# ESP8266_firstBringup.net
KiCad netlist of a schematic drawn in EAGLE
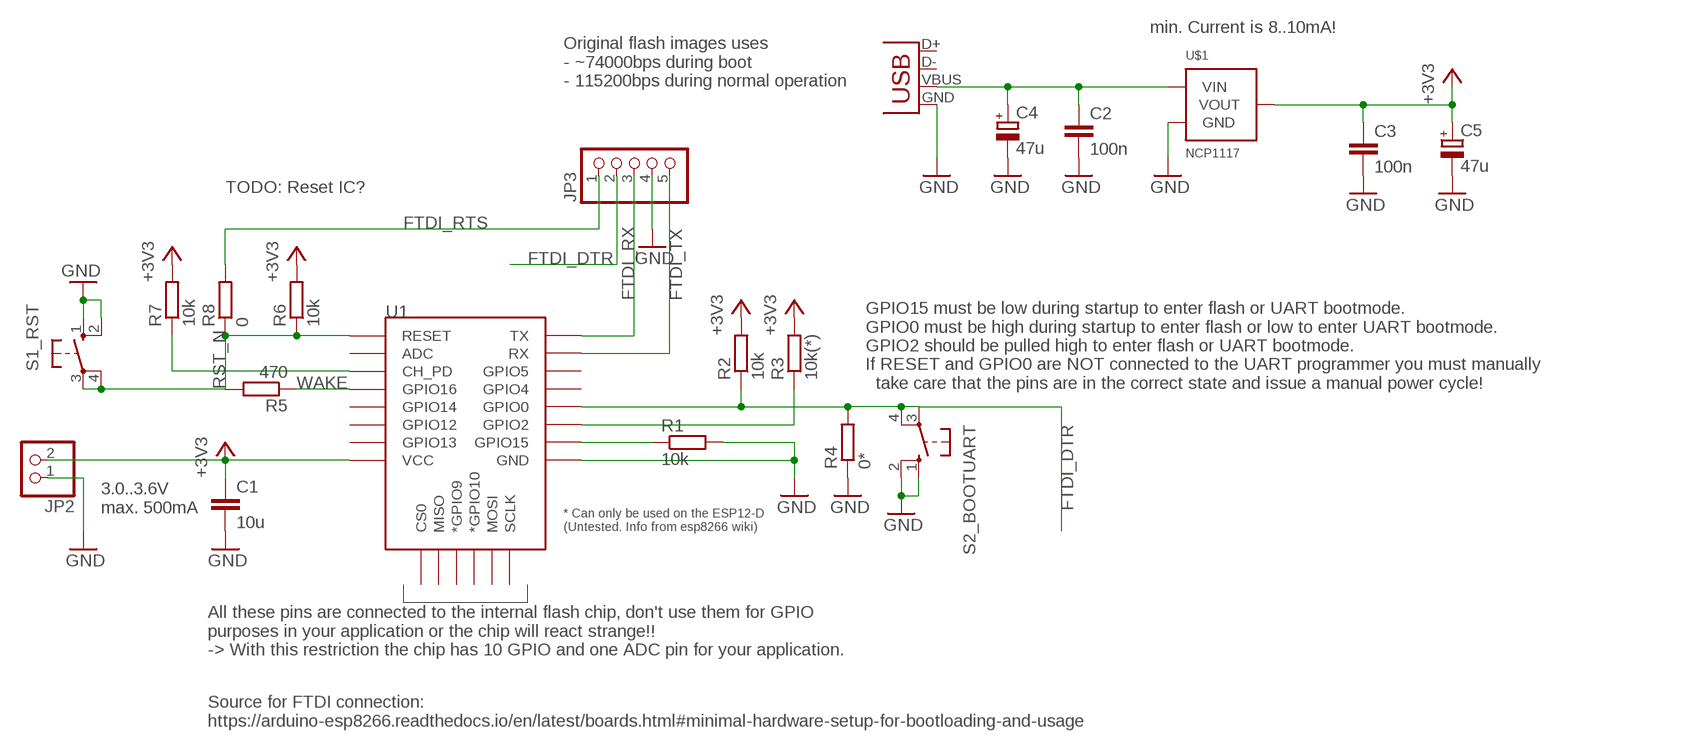
[diagram p0: schematic, sheet 1]

(export (version "E")
  (design (tool "Eeschema 10.0.6"))
  (components
    (comp (ref "C1")
      (value "10u")
      (footprint "eagle-import:C0805")
      (libsource (lib "eagle-import") (part "C-EUC0805"))
    )
    (comp (ref "C2")
      (value "100n")
      (footprint "eagle-import:C0603")
      (libsource (lib "eagle-import") (part "C-EUC0603"))
    )
    (comp (ref "C3")
      (value "100n")
      (footprint "eagle-import:C0603")
      (libsource (lib "eagle-import") (part "C-EUC0603"))
    )
    (comp (ref "C4")
      (value "47u")
      (footprint "eagle-import:E2,5-6")
      (libsource (lib "eagle-import") (part "CPOL-EUE2.5-6"))
    )
    (comp (ref "C5")
      (value "47u")
      (footprint "eagle-import:E2,5-6")
      (libsource (lib "eagle-import") (part "CPOL-EUE2.5-6"))
    )
    (comp (ref "JP2")
      (value "PINHD-1X2")
      (footprint "eagle-import:1X02")
      (libsource (lib "eagle-import") (part "PINHD-1X2"))
    )
    (comp (ref "JP3")
      (value "PINHD-1X5")
      (footprint "eagle-import:1X05")
      (libsource (lib "eagle-import") (part "PINHD-1X5"))
    )
    (comp (ref "R1")
      (value "10k")
      (footprint "eagle-import:R0402")
      (libsource (lib "eagle-import") (part "R-EU_R0402"))
    )
    (comp (ref "R2")
      (value "10k")
      (footprint "eagle-import:R0402")
      (libsource (lib "eagle-import") (part "R-EU_R0402"))
    )
    (comp (ref "R3")
      (value "10k(*)")
      (footprint "eagle-import:R0402")
      (libsource (lib "eagle-import") (part "R-EU_R0402"))
    )
    (comp (ref "R4")
      (value "0*")
      (footprint "eagle-import:R0402")
      (libsource (lib "eagle-import") (part "R-EU_R0402"))
    )
    (comp (ref "R5")
      (value "470")
      (footprint "eagle-import:R0402")
      (libsource (lib "eagle-import") (part "R-EU_R0402"))
    )
    (comp (ref "R6")
      (value "10k")
      (footprint "eagle-import:R0402")
      (libsource (lib "eagle-import") (part "R-EU_R0402"))
    )
    (comp (ref "R7")
      (value "10k")
      (footprint "eagle-import:R0402")
      (libsource (lib "eagle-import") (part "R-EU_R0402"))
    )
    (comp (ref "R8")
      (value "0")
      (footprint "eagle-import:R0402")
      (libsource (lib "eagle-import") (part "R-EU_R0402"))
    )
    (comp (ref "S1_RST")
      (value "10-XX")
      (footprint "eagle-import:B3F-10XX")
      (fields (field (name "MPN") "B3F-1000"))
      (libsource (lib "eagle-import") (part "10-XX"))
    )
    (comp (ref "S2_BOOTUART")
      (value "10-XX")
      (footprint "eagle-import:B3F-10XX")
      (fields (field (name "MPN") "B3F-1000"))
      (libsource (lib "eagle-import") (part "10-XX"))
    )
    (comp (ref "U$1")
      (value "NCP1117")
      (footprint "eagle-import:SOT223")
      (libsource (lib "eagle-import") (part "NCP1117"))
    )
    (comp (ref "U1")
      (value "ESP12ESMD")
      (footprint "eagle-import:ESP12E-SMD")
      (libsource (lib "eagle-import") (part "ESP12ESMD"))
    )
    (comp (ref "X1")
      (value "USBPTH")
      (footprint "eagle-import:USB-B-PTH")
      (libsource (lib "eagle-import") (part "USBPTH"))
    )
  )
  (nets
    (net (code "1") (name "+3V3") (class "Default")
      (node (ref "C1") (pin "1") (pinfunction "1_1") (pintype "passive"))
      (node (ref "C3") (pin "1") (pinfunction "1_1") (pintype "passive"))
      (node (ref "C5") (pin "+") (pinfunction "+_+") (pintype "passive"))
      (node (ref "JP2") (pin "2") (pinfunction "2_2") (pintype "passive"))
      (node (ref "R2") (pin "2") (pinfunction "2_2") (pintype "passive"))
      (node (ref "R3") (pin "2") (pinfunction "2_2") (pintype "passive"))
      (node (ref "R6") (pin "2") (pinfunction "2_2") (pintype "passive"))
      (node (ref "R7") (pin "2") (pinfunction "2_2") (pintype "passive"))
      (node (ref "U$1") (pin "2") (pinfunction "VOUT_2") (pintype "bidirectional"))
      (node (ref "U$1") (pin "4") (pinfunction "VOUT_4") (pintype "bidirectional"))
      (node (ref "U1") (pin "VCC") (pinfunction "VCC_VCC") (pintype "bidirectional"))
    )
    (net (code "2") (name "/FTDI_DTR") (class "Default")
      (node (ref "JP3") (pin "2") (pinfunction "2_2") (pintype "passive"))
      (node (ref "R2") (pin "1") (pinfunction "1_1") (pintype "passive"))
      (node (ref "R4") (pin "2") (pinfunction "2_2") (pintype "passive"))
      (node (ref "S2_BOOTUART") (pin "3") (pinfunction "P_3") (pintype "passive"))
      (node (ref "S2_BOOTUART") (pin "4") (pinfunction "P1_4") (pintype "passive"))
      (node (ref "U1") (pin "GPIO0") (pinfunction "GPIO0_GPIO0") (pintype "bidirectional"))
    )
    (net (code "3") (name "/FTDI_RTS") (class "Default")
      (node (ref "JP3") (pin "1") (pinfunction "1_1") (pintype "passive"))
      (node (ref "R8") (pin "2") (pinfunction "2_2") (pintype "passive"))
    )
    (net (code "4") (name "/FTDI_RX") (class "Default")
      (node (ref "JP3") (pin "3") (pinfunction "3_3") (pintype "passive"))
      (node (ref "U1") (pin "TXD0") (pinfunction "TX_TXD0") (pintype "bidirectional"))
    )
    (net (code "5") (name "/FTDI_TX") (class "Default")
      (node (ref "JP3") (pin "5") (pinfunction "5_5") (pintype "passive"))
      (node (ref "U1") (pin "RXD0") (pinfunction "RX_RXD0") (pintype "bidirectional"))
    )
    (net (code "6") (name "/RST_N") (class "Default")
      (node (ref "R5") (pin "2") (pinfunction "2_2") (pintype "passive"))
      (node (ref "R6") (pin "1") (pinfunction "1_1") (pintype "passive"))
      (node (ref "R8") (pin "1") (pinfunction "1_1") (pintype "passive"))
      (node (ref "S1_RST") (pin "3") (pinfunction "P_3") (pintype "passive"))
      (node (ref "S1_RST") (pin "4") (pinfunction "P1_4") (pintype "passive"))
      (node (ref "U1") (pin "RESET") (pinfunction "RESET_RESET") (pintype "bidirectional"))
    )
    (net (code "7") (name "/WAKE") (class "Default")
      (node (ref "R5") (pin "1") (pinfunction "1_1") (pintype "passive"))
      (node (ref "U1") (pin "GPIO16") (pinfunction "GPIO16_GPIO16") (pintype "bidirectional"))
    )
    (net (code "8") (name "GND") (class "Default")
      (node (ref "C1") (pin "2") (pinfunction "2_2") (pintype "passive"))
      (node (ref "C2") (pin "2") (pinfunction "2_2") (pintype "passive"))
      (node (ref "C3") (pin "2") (pinfunction "2_2") (pintype "passive"))
      (node (ref "C4") (pin "-") (pinfunction "-_-") (pintype "passive"))
      (node (ref "C5") (pin "-") (pinfunction "-_-") (pintype "passive"))
      (node (ref "JP2") (pin "1") (pinfunction "1_1") (pintype "passive"))
      (node (ref "JP3") (pin "4") (pinfunction "4_4") (pintype "passive"))
      (node (ref "R1") (pin "2") (pinfunction "2_2") (pintype "passive"))
      (node (ref "R4") (pin "1") (pinfunction "1_1") (pintype "passive"))
      (node (ref "S1_RST") (pin "1") (pinfunction "S_1") (pintype "passive"))
      (node (ref "S1_RST") (pin "2") (pinfunction "S1_2") (pintype "passive"))
      (node (ref "S2_BOOTUART") (pin "1") (pinfunction "S_1") (pintype "passive"))
      (node (ref "S2_BOOTUART") (pin "2") (pinfunction "S1_2") (pintype "passive"))
      (node (ref "U$1") (pin "1") (pinfunction "GND_1") (pintype "bidirectional"))
      (node (ref "U1") (pin "GND") (pinfunction "GND_GND") (pintype "bidirectional"))
      (node (ref "X1") (pin "GND") (pinfunction "GND_GND") (pintype "bidirectional"))
    )
    (net (code "9") (name "Net-(R1-Pad1)") (class "Default")
      (node (ref "R1") (pin "1") (pinfunction "1_1") (pintype "passive"))
      (node (ref "U1") (pin "GPIO15") (pinfunction "GPIO15_GPIO15") (pintype "bidirectional"))
    )
    (net (code "10") (name "Net-(R3-Pad1)") (class "Default")
      (node (ref "R3") (pin "1") (pinfunction "1_1") (pintype "passive"))
      (node (ref "U1") (pin "GPIO2") (pinfunction "GPIO2_GPIO2") (pintype "bidirectional"))
    )
    (net (code "11") (name "Net-(R7-Pad1)") (class "Default")
      (node (ref "R7") (pin "1") (pinfunction "1_1") (pintype "passive"))
      (node (ref "U1") (pin "CH_PD") (pinfunction "CH_PD_CH_PD") (pintype "bidirectional"))
    )
    (net (code "12") (name "Net-(U$1-VIN)") (class "Default")
      (node (ref "C2") (pin "1") (pinfunction "1_1") (pintype "passive"))
      (node (ref "C4") (pin "+") (pinfunction "+_+") (pintype "passive"))
      (node (ref "U$1") (pin "3") (pinfunction "VIN_3") (pintype "bidirectional"))
      (node (ref "X1") (pin "VBUS") (pinfunction "VBUS_VBUS") (pintype "bidirectional"))
    )
    (net (code "13") (name "unconnected-(U1-*GPIO9-PadGPIO9)") (class "Default")
      (node (ref "U1") (pin "GPIO9") (pinfunction "*GPIO9_GPIO9") (pintype "bidirectional"))
    )
    (net (code "14") (name "unconnected-(U1-*GPIO10-PadGPIO10)") (class "Default")
      (node (ref "U1") (pin "GPIO10") (pinfunction "*GPIO10_GPIO10") (pintype "bidirectional"))
    )
    (net (code "15") (name "unconnected-(U1-PadADC)") (class "Default")
      (node (ref "U1") (pin "ADC") (pinfunction "ADC_ADC") (pintype "bidirectional"))
    )
    (net (code "16") (name "unconnected-(U1-PadCS0)") (class "Default")
      (node (ref "U1") (pin "CS0") (pinfunction "CS0_CS0") (pintype "bidirectional"))
    )
    (net (code "17") (name "unconnected-(U1-PadGPIO4)") (class "Default")
      (node (ref "U1") (pin "GPIO4") (pinfunction "GPIO4_GPIO4") (pintype "bidirectional"))
    )
    (net (code "18") (name "unconnected-(U1-PadGPIO5)") (class "Default")
      (node (ref "U1") (pin "GPIO5") (pinfunction "GPIO5_GPIO5") (pintype "bidirectional"))
    )
    (net (code "19") (name "unconnected-(U1-PadGPIO12)") (class "Default")
      (node (ref "U1") (pin "GPIO12") (pinfunction "GPIO12_GPIO12") (pintype "bidirectional"))
    )
    (net (code "20") (name "unconnected-(U1-PadGPIO13)") (class "Default")
      (node (ref "U1") (pin "GPIO13") (pinfunction "GPIO13_GPIO13") (pintype "bidirectional"))
    )
    (net (code "21") (name "unconnected-(U1-PadGPIO14)") (class "Default")
      (node (ref "U1") (pin "GPIO14") (pinfunction "GPIO14_GPIO14") (pintype "bidirectional"))
    )
    (net (code "22") (name "unconnected-(U1-PadMISO)") (class "Default")
      (node (ref "U1") (pin "MISO") (pinfunction "MISO_MISO") (pintype "bidirectional"))
    )
    (net (code "23") (name "unconnected-(U1-PadMOSI)") (class "Default")
      (node (ref "U1") (pin "MOSI") (pinfunction "MOSI_MOSI") (pintype "bidirectional"))
    )
    (net (code "24") (name "unconnected-(U1-PadSCLK)") (class "Default")
      (node (ref "U1") (pin "SCLK") (pinfunction "SCLK_SCLK") (pintype "bidirectional"))
    )
    (net (code "25") (name "unconnected-(X1-PadD+)") (class "Default")
      (node (ref "X1") (pin "D+") (pinfunction "D+_D+") (pintype "bidirectional"))
    )
    (net (code "26") (name "unconnected-(X1-PadD-)") (class "Default")
      (node (ref "X1") (pin "D-") (pinfunction "D-_D-") (pintype "bidirectional"))
    )
  )
)
